# RPi-HAT_BUS-Controller_V0_1.net
KiCad netlist of a schematic drawn in EAGLE
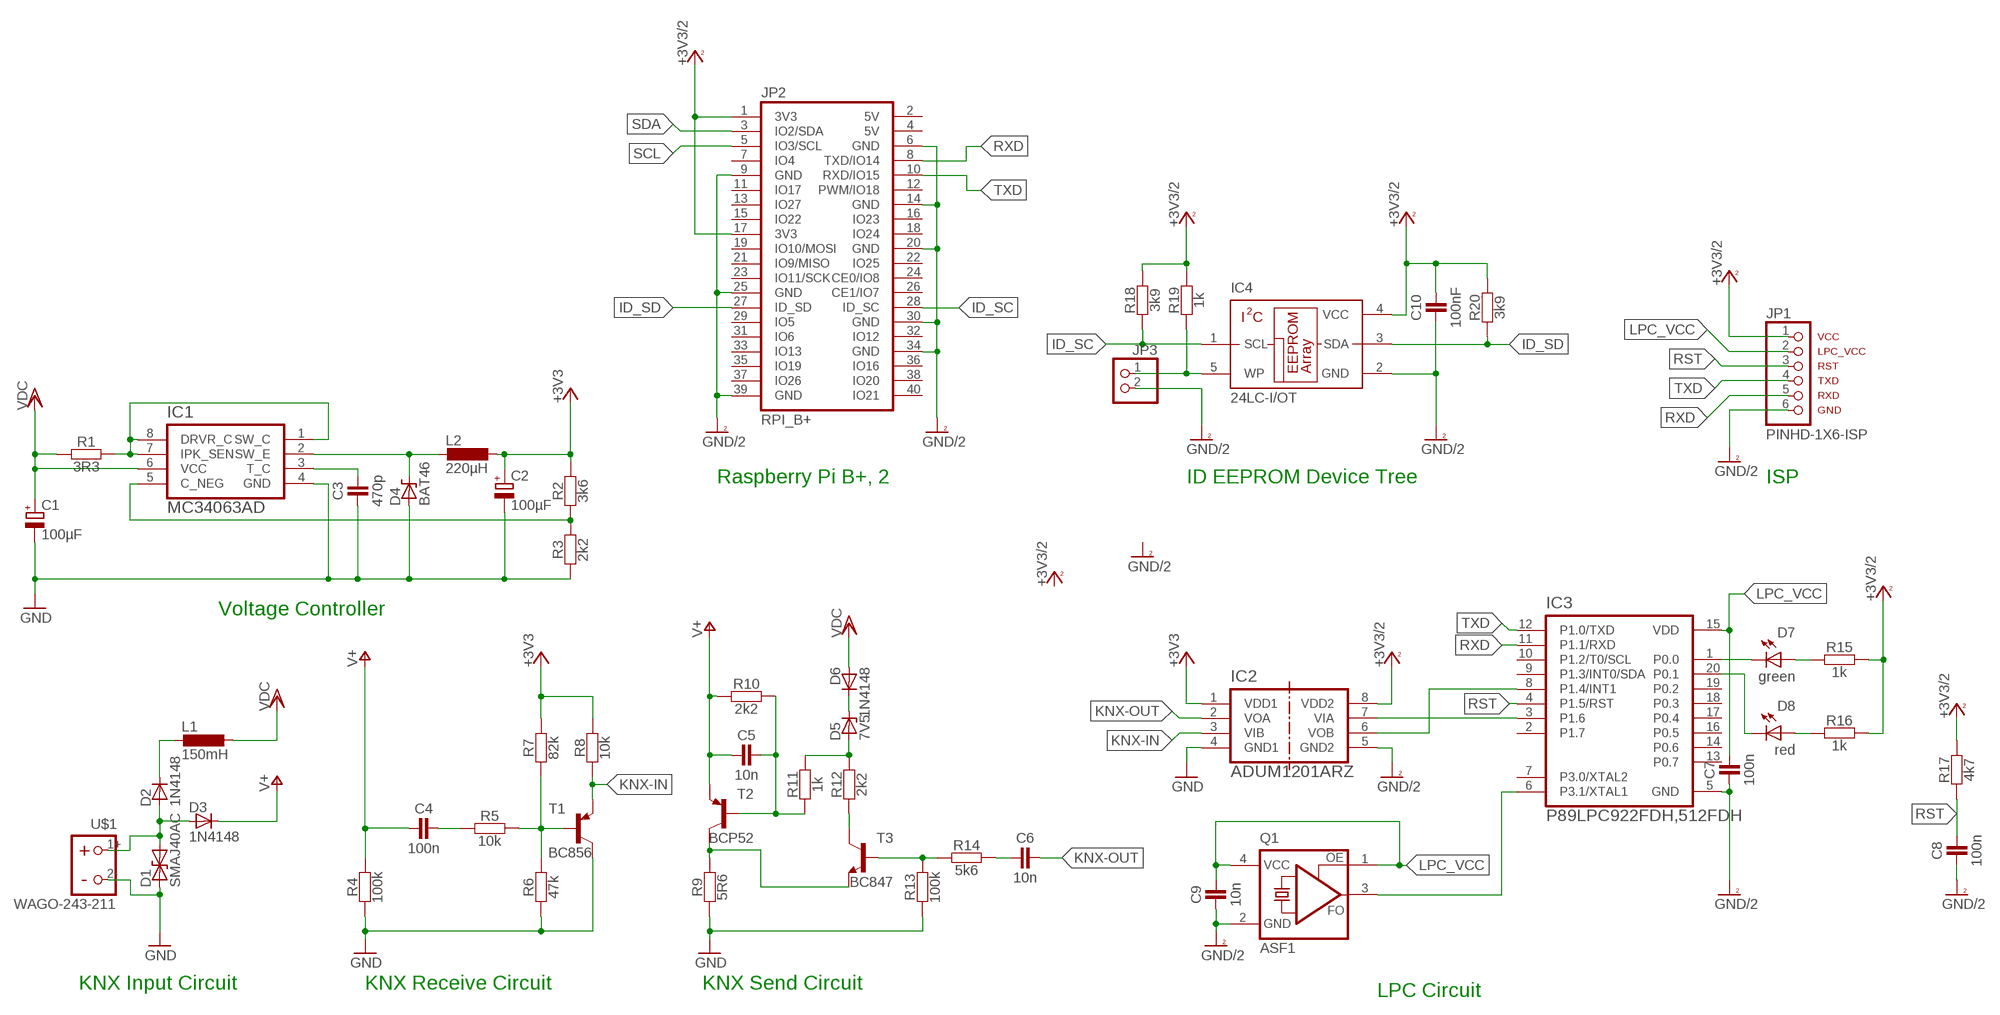
[diagram p0: schematic, sheet 1]

(export (version "E")
  (design (tool "Eeschema 10.0.6"))
  (components
    (comp (ref "C1")
      (value "100µF")
      (footprint "eagle-import:PANASONIC_D")
      (libsource (lib "eagle-import") (part "100µF,35V"))
    )
    (comp (ref "C2")
      (value "100µF")
      (footprint "eagle-import:PANASONIC_C")
      (libsource (lib "eagle-import") (part "100µF,6.3V"))
    )
    (comp (ref "C3")
      (value "470p")
      (footprint "eagle-import:R1206")
      (libsource (lib "eagle-import") (part "CAPACITORC1206"))
    )
    (comp (ref "C4")
      (value "100n")
      (footprint "eagle-import:R1206")
      (libsource (lib "eagle-import") (part "CAPACITORC1206"))
    )
    (comp (ref "C5")
      (value "10n")
      (footprint "eagle-import:R1206")
      (libsource (lib "eagle-import") (part "CAPACITORC1206"))
    )
    (comp (ref "C6")
      (value "10n")
      (footprint "eagle-import:R1206")
      (libsource (lib "eagle-import") (part "CAPACITORC1206"))
    )
    (comp (ref "C7")
      (value "100n")
      (footprint "eagle-import:R1206")
      (libsource (lib "eagle-import") (part "CAPACITORC1206"))
    )
    (comp (ref "C8")
      (value "100n")
      (footprint "eagle-import:R1206")
      (libsource (lib "eagle-import") (part "CAPACITORC1206"))
    )
    (comp (ref "C9")
      (value "10n")
      (footprint "eagle-import:R1206")
      (libsource (lib "eagle-import") (part "CAPACITORC1206"))
    )
    (comp (ref "C10")
      (value "100nF")
      (footprint "eagle-import:R1206")
      (libsource (lib "eagle-import") (part "CAPACITORC1206"))
    )
    (comp (ref "D1")
      (value "SMAJ40AC")
      (footprint "eagle-import:DO-214AC")
      (libsource (lib "eagle-import") (part "SMAJ40AC"))
    )
    (comp (ref "D2")
      (value "1N4148")
      (footprint "eagle-import:MINIMELF")
      (libsource (lib "eagle-import") (part "1N4148MINIMELF"))
    )
    (comp (ref "D3")
      (value "1N4148")
      (footprint "eagle-import:MINIMELF")
      (libsource (lib "eagle-import") (part "1N4148MINIMELF"))
    )
    (comp (ref "D4")
      (value "BAT46")
      (footprint "eagle-import:MINIMELF")
      (libsource (lib "eagle-import") (part "BAT46"))
    )
    (comp (ref "D5")
      (value "7V5")
      (footprint "eagle-import:MINIMELF")
      (libsource (lib "eagle-import") (part "Z-DIODE"))
    )
    (comp (ref "D6")
      (value "1N4148")
      (footprint "eagle-import:MINIMELF")
      (libsource (lib "eagle-import") (part "Diode_for_Selfbus-Projects_1N4148MINIMELF"))
    )
    (comp (ref "D7")
      (value "green")
      (footprint "eagle-import:CHIPLED_1206")
      (libsource (lib "eagle-import") (part "LED1206"))
    )
    (comp (ref "D8")
      (value "red")
      (footprint "eagle-import:CHIPLED_1206")
      (libsource (lib "eagle-import") (part "LED1206"))
    )
    (comp (ref "IC1")
      (value "MC34063AD")
      (footprint "eagle-import:SOIC127P600X175-8N")
      (libsource (lib "eagle-import") (part "MC34063AD"))
    )
    (comp (ref "IC2")
      (value "ADUM1201ARZ")
      (footprint "eagle-import:SOIC127P600X175-8N")
      (libsource (lib "eagle-import") (part "ADUM1201ARZ"))
    )
    (comp (ref "IC3")
      (value "P89LPC922FDH,512FDH")
      (footprint "eagle-import:SOP65P640X110-20N")
      (fields (field (name "MPN") "P89LPC922FDH,512"))
      (libsource (lib "eagle-import") (part "P89LPC922FDH,512FDH"))
    )
    (comp (ref "IC4")
      (value "24LC-I/OT")
      (footprint "eagle-import:SOT23-5")
      (libsource (lib "eagle-import") (part "24LC-I/OT"))
    )
    (comp (ref "JP1")
      (value "PINHD-1X6-ISP")
      (footprint "eagle-import:1X06")
      (libsource (lib "eagle-import") (part "PINHD-1X6-ISP"))
    )
    (comp (ref "JP2")
      (value "RPI_B+")
      (footprint "eagle-import:RPI-B+HAT")
      (libsource (lib "eagle-import") (part "RPI_B+"))
    )
    (comp (ref "JP3")
      (value "PINHD-1X2")
      (footprint "eagle-import:1X02")
      (libsource (lib "eagle-import") (part "PINHD-1X2"))
    )
    (comp (ref "L1")
      (value "150mH")
      (footprint "eagle-import:11P-L1")
      (libsource (lib "eagle-import") (part "150MH-L11PL1"))
    )
    (comp (ref "L2")
      (value "220µH")
      (footprint "eagle-import:2200-11.43")
      (libsource (lib "eagle-import") (part "220µH-SMCC11.43"))
    )
    (comp (ref "Q1")
      (value "ASF1")
      (footprint "eagle-import:ASF")
      (libsource (lib "eagle-import") (part "ASF1"))
    )
    (comp (ref "R1")
      (value "3R3")
      (footprint "eagle-import:R1206")
      (libsource (lib "eagle-import") (part "RESISTORR1206"))
    )
    (comp (ref "R2")
      (value "3k6")
      (footprint "eagle-import:R1206")
      (libsource (lib "eagle-import") (part "RESISTORR1206"))
    )
    (comp (ref "R3")
      (value "2k2")
      (footprint "eagle-import:R1206")
      (libsource (lib "eagle-import") (part "RESISTORR1206"))
    )
    (comp (ref "R4")
      (value "100k")
      (footprint "eagle-import:R1206")
      (libsource (lib "eagle-import") (part "RESISTORR1206"))
    )
    (comp (ref "R5")
      (value "10k")
      (footprint "eagle-import:R1206")
      (libsource (lib "eagle-import") (part "RESISTORR1206"))
    )
    (comp (ref "R6")
      (value "47k")
      (footprint "eagle-import:R1206")
      (libsource (lib "eagle-import") (part "RESISTORR1206"))
    )
    (comp (ref "R7")
      (value "82k")
      (footprint "eagle-import:R1206")
      (libsource (lib "eagle-import") (part "RESISTORR1206"))
    )
    (comp (ref "R8")
      (value "10k")
      (footprint "eagle-import:R1206")
      (libsource (lib "eagle-import") (part "RESISTORR1206"))
    )
    (comp (ref "R9")
      (value "5R6")
      (footprint "eagle-import:R1206")
      (libsource (lib "eagle-import") (part "RESISTORR1206"))
    )
    (comp (ref "R10")
      (value "2k2")
      (footprint "eagle-import:R1206")
      (libsource (lib "eagle-import") (part "RESISTORR1206"))
    )
    (comp (ref "R11")
      (value "1k")
      (footprint "eagle-import:R1206")
      (libsource (lib "eagle-import") (part "RESISTORR1206"))
    )
    (comp (ref "R12")
      (value "2k2")
      (footprint "eagle-import:R1206")
      (libsource (lib "eagle-import") (part "RESISTORR1206"))
    )
    (comp (ref "R13")
      (value "100k")
      (footprint "eagle-import:R1206")
      (libsource (lib "eagle-import") (part "RESISTORR1206"))
    )
    (comp (ref "R14")
      (value "5k6")
      (footprint "eagle-import:R1206")
      (libsource (lib "eagle-import") (part "RESISTORR1206"))
    )
    (comp (ref "R15")
      (value "1k")
      (footprint "eagle-import:R1206")
      (libsource (lib "eagle-import") (part "RESISTORR1206"))
    )
    (comp (ref "R16")
      (value "1k")
      (footprint "eagle-import:R1206")
      (libsource (lib "eagle-import") (part "RESISTORR1206"))
    )
    (comp (ref "R17")
      (value "4k7")
      (footprint "eagle-import:R1206")
      (libsource (lib "eagle-import") (part "RESISTORR1206"))
    )
    (comp (ref "R18")
      (value "3k9")
      (footprint "eagle-import:R1206")
      (libsource (lib "eagle-import") (part "RESISTORR1206"))
    )
    (comp (ref "R19")
      (value "1k")
      (footprint "eagle-import:R1206")
      (libsource (lib "eagle-import") (part "RESISTORR1206"))
    )
    (comp (ref "R20")
      (value "3k9")
      (footprint "eagle-import:R1206")
      (libsource (lib "eagle-import") (part "RESISTORR1206"))
    )
    (comp (ref "T1")
      (value "BC856")
      (footprint "eagle-import:SOT23")
      (libsource (lib "eagle-import") (part "PNPBC856"))
    )
    (comp (ref "T2")
      (value "BCP52")
      (footprint "eagle-import:SOT223")
      (libsource (lib "eagle-import") (part "PNPBCP52"))
    )
    (comp (ref "T3")
      (value "BC847")
      (footprint "eagle-import:SOT23")
      (libsource (lib "eagle-import") (part "NPN-BC847"))
    )
    (comp (ref "U$1")
      (value "WAGO-243-211")
      (footprint "eagle-import:WAGO-243-211")
      (libsource (lib "eagle-import") (part "WAGO-243-211"))
    )
  )
  (nets
    (net (code "1") (name "+3V3") (class "Default")
      (node (ref "C2") (pin "+") (pinfunction "+_+") (pintype "passive"))
      (node (ref "IC2") (pin "1") (pinfunction "VDD1_1") (pintype "power_in"))
      (node (ref "L2") (pin "1") (pinfunction "1_1") (pintype "passive"))
      (node (ref "R2") (pin "2") (pinfunction "2_2") (pintype "passive"))
      (node (ref "R7") (pin "2") (pinfunction "2_2") (pintype "passive"))
      (node (ref "R8") (pin "2") (pinfunction "2_2") (pintype "passive"))
    )
    (net (code "2") (name "+3V3{slash}2") (class "Default")
      (node (ref "C10") (pin "2") (pinfunction "2_2") (pintype "passive"))
      (node (ref "IC2") (pin "8") (pinfunction "VDD2_8") (pintype "power_in"))
      (node (ref "IC4") (pin "4") (pinfunction "VCC_4") (pintype "power_in"))
      (node (ref "JP1") (pin "1") (pinfunction "1_1") (pintype "passive"))
      (node (ref "JP2") (pin "1") (pinfunction "3V3_1") (pintype "passive"))
      (node (ref "JP2") (pin "17") (pinfunction "3V3_17") (pintype "passive"))
      (node (ref "R15") (pin "2") (pinfunction "2_2") (pintype "passive"))
      (node (ref "R16") (pin "2") (pinfunction "2_2") (pintype "passive"))
      (node (ref "R17") (pin "2") (pinfunction "2_2") (pintype "passive"))
      (node (ref "R18") (pin "2") (pinfunction "2_2") (pintype "passive"))
      (node (ref "R19") (pin "2") (pinfunction "2_2") (pintype "passive"))
      (node (ref "R20") (pin "2") (pinfunction "2_2") (pintype "passive"))
    )
    (net (code "3") (name "GND") (class "Default")
      (node (ref "C1") (pin "-") (pinfunction "-_-") (pintype "passive"))
      (node (ref "C2") (pin "-") (pinfunction "-_-") (pintype "passive"))
      (node (ref "C3") (pin "1") (pinfunction "1_1") (pintype "passive"))
      (node (ref "D1") (pin "A") (pinfunction "A_A") (pintype "passive"))
      (node (ref "D4") (pin "A") (pinfunction "A_A") (pintype "passive"))
      (node (ref "IC1") (pin "4") (pinfunction "GND_4") (pintype "passive"))
      (node (ref "IC2") (pin "4") (pinfunction "GND1_4") (pintype "passive"))
      (node (ref "R13") (pin "1") (pinfunction "1_1") (pintype "passive"))
      (node (ref "R3") (pin "1") (pinfunction "1_1") (pintype "passive"))
      (node (ref "R4") (pin "1") (pinfunction "1_1") (pintype "passive"))
      (node (ref "R6") (pin "1") (pinfunction "1_1") (pintype "passive"))
      (node (ref "R9") (pin "1") (pinfunction "1_1") (pintype "passive"))
      (node (ref "T1") (pin "3") (pinfunction "C_3") (pintype "passive"))
      (node (ref "U$1") (pin "2-") (pinfunction "2-_2-") (pintype "passive"))
    )
    (net (code "4") (name "GND{slash}2") (class "Default")
      (node (ref "C10") (pin "1") (pinfunction "1_1") (pintype "passive"))
      (node (ref "C7") (pin "1") (pinfunction "1_1") (pintype "passive"))
      (node (ref "C8") (pin "1") (pinfunction "1_1") (pintype "passive"))
      (node (ref "C9") (pin "1") (pinfunction "1_1") (pintype "passive"))
      (node (ref "IC2") (pin "5") (pinfunction "GND2_5") (pintype "passive"))
      (node (ref "IC3") (pin "5") (pinfunction "GND_5") (pintype "passive"))
      (node (ref "IC4") (pin "2") (pinfunction "GND_2") (pintype "power_in"))
      (node (ref "JP1") (pin "6") (pinfunction "6_6") (pintype "passive"))
      (node (ref "JP2") (pin "14") (pinfunction "GND_14") (pintype "passive"))
      (node (ref "JP2") (pin "20") (pinfunction "GND_20") (pintype "passive"))
      (node (ref "JP2") (pin "25") (pinfunction "GND_25") (pintype "passive"))
      (node (ref "JP2") (pin "30") (pinfunction "GND_30") (pintype "bidirectional"))
      (node (ref "JP2") (pin "34") (pinfunction "GND_34") (pintype "bidirectional"))
      (node (ref "JP2") (pin "39") (pinfunction "GND_39") (pintype "bidirectional"))
      (node (ref "JP2") (pin "6") (pinfunction "GND_6") (pintype "passive"))
      (node (ref "JP2") (pin "9") (pinfunction "GND_9") (pintype "passive"))
      (node (ref "JP3") (pin "2") (pinfunction "2_2") (pintype "passive"))
      (node (ref "Q1") (pin "2") (pinfunction "GND_2") (pintype "power_in"))
    )
    (net (code "5") (name "ID_SC") (class "Default")
      (node (ref "IC4") (pin "1") (pinfunction "SCL_1") (pintype "bidirectional"))
      (node (ref "JP2") (pin "28") (pinfunction "ID_SC_28") (pintype "bidirectional"))
      (node (ref "R18") (pin "1") (pinfunction "1_1") (pintype "passive"))
    )
    (net (code "6") (name "ID_SD") (class "Default")
      (node (ref "IC4") (pin "3") (pinfunction "SDA_3") (pintype "bidirectional"))
      (node (ref "JP2") (pin "27") (pinfunction "ID_SD_27") (pintype "bidirectional"))
      (node (ref "R20") (pin "1") (pinfunction "1_1") (pintype "passive"))
    )
    (net (code "7") (name "KNX-IN") (class "Default")
      (node (ref "IC2") (pin "3") (pinfunction "VIB_3") (pintype "input"))
      (node (ref "R8") (pin "1") (pinfunction "1_1") (pintype "passive"))
      (node (ref "T1") (pin "2") (pinfunction "E_2") (pintype "passive"))
    )
    (net (code "8") (name "KNX-OUT") (class "Default")
      (node (ref "C6") (pin "2") (pinfunction "2_2") (pintype "passive"))
      (node (ref "IC2") (pin "2") (pinfunction "VOA_2") (pintype "output"))
    )
    (net (code "9") (name "LPC_VCC") (class "Default")
      (node (ref "C7") (pin "2") (pinfunction "2_2") (pintype "passive"))
      (node (ref "C9") (pin "2") (pinfunction "2_2") (pintype "passive"))
      (node (ref "IC3") (pin "15") (pinfunction "VDD_15") (pintype "power_in"))
      (node (ref "JP1") (pin "2") (pinfunction "2_2") (pintype "passive"))
      (node (ref "Q1") (pin "1") (pinfunction "OE_1") (pintype "input"))
      (node (ref "Q1") (pin "4") (pinfunction "VCC_4") (pintype "power_in"))
    )
    (net (code "10") (name "Net-(C4-Pad2)") (class "Default")
      (node (ref "C4") (pin "2") (pinfunction "2_2") (pintype "passive"))
      (node (ref "R5") (pin "1") (pinfunction "1_1") (pintype "passive"))
    )
    (net (code "11") (name "Net-(C6-Pad1)") (class "Default")
      (node (ref "C6") (pin "1") (pinfunction "1_1") (pintype "passive"))
      (node (ref "R14") (pin "2") (pinfunction "2_2") (pintype "passive"))
    )
    (net (code "12") (name "Net-(D1-PadC)") (class "Default")
      (node (ref "D1") (pin "C") (pinfunction "C_C") (pintype "passive"))
      (node (ref "D2") (pin "A") (pinfunction "A_A") (pintype "passive"))
      (node (ref "D3") (pin "A") (pinfunction "A_A") (pintype "passive"))
      (node (ref "U$1") (pin "1+") (pinfunction "1+_1+") (pintype "passive"))
    )
    (net (code "13") (name "Net-(D2-PadC)") (class "Default")
      (node (ref "D2") (pin "C") (pinfunction "C_C") (pintype "passive"))
      (node (ref "L1") (pin "2") (pinfunction "2_2") (pintype "passive"))
    )
    (net (code "14") (name "Net-(D5-PadA)") (class "Default")
      (node (ref "D5") (pin "A") (pinfunction "A_A") (pintype "passive"))
      (node (ref "R11") (pin "2") (pinfunction "2_2") (pintype "passive"))
      (node (ref "R12") (pin "2") (pinfunction "2_2") (pintype "passive"))
    )
    (net (code "15") (name "Net-(D5-PadC)") (class "Default")
      (node (ref "D5") (pin "C") (pinfunction "C_C") (pintype "passive"))
      (node (ref "D6") (pin "C") (pinfunction "C_C") (pintype "passive"))
    )
    (net (code "16") (name "Net-(D7-PadA)") (class "Default")
      (node (ref "D7") (pin "A") (pinfunction "A_A") (pintype "passive"))
      (node (ref "R15") (pin "1") (pinfunction "1_1") (pintype "passive"))
    )
    (net (code "17") (name "Net-(D8-PadA)") (class "Default")
      (node (ref "D8") (pin "A") (pinfunction "A_A") (pintype "passive"))
      (node (ref "R16") (pin "1") (pinfunction "1_1") (pintype "passive"))
    )
    (net (code "18") (name "Net-(IC1-C_NEG)") (class "Default")
      (node (ref "IC1") (pin "5") (pinfunction "C_NEG_5") (pintype "input"))
      (node (ref "R2") (pin "1") (pinfunction "1_1") (pintype "passive"))
      (node (ref "R3") (pin "2") (pinfunction "2_2") (pintype "passive"))
    )
    (net (code "19") (name "Net-(IC1-DRVR_C)") (class "Default")
      (node (ref "IC1") (pin "1") (pinfunction "SW_C_1") (pintype "output"))
      (node (ref "IC1") (pin "7") (pinfunction "IPK_SEN_7") (pintype "input"))
      (node (ref "IC1") (pin "8") (pinfunction "DRVR_C_8") (pintype "input"))
      (node (ref "R1") (pin "2") (pinfunction "2_2") (pintype "passive"))
    )
    (net (code "20") (name "Net-(IC1-SW_E)") (class "Default")
      (node (ref "D4") (pin "C") (pinfunction "C_C") (pintype "passive"))
      (node (ref "IC1") (pin "2") (pinfunction "SW_E_2") (pintype "output"))
      (node (ref "L2") (pin "2") (pinfunction "2_2") (pintype "passive"))
    )
    (net (code "21") (name "Net-(IC1-T_C)") (class "Default")
      (node (ref "C3") (pin "2") (pinfunction "2_2") (pintype "passive"))
      (node (ref "IC1") (pin "3") (pinfunction "T_C_3") (pintype "output"))
    )
    (net (code "22") (name "Net-(IC2-VIA)") (class "Default")
      (node (ref "IC2") (pin "7") (pinfunction "VIA_7") (pintype "input"))
      (node (ref "IC3") (pin "3") (pinfunction "P1.6_3") (pintype "bidirectional"))
    )
    (net (code "23") (name "Net-(IC2-VOB)") (class "Default")
      (node (ref "IC2") (pin "6") (pinfunction "VOB_6") (pintype "output"))
      (node (ref "IC3") (pin "8") (pinfunction "P1.4/INT1_8") (pintype "bidirectional"))
    )
    (net (code "24") (name "Net-(IC3-P0.0)") (class "Default")
      (node (ref "D7") (pin "C") (pinfunction "C_C") (pintype "passive"))
      (node (ref "IC3") (pin "1") (pinfunction "P0.0_1") (pintype "bidirectional"))
    )
    (net (code "25") (name "Net-(IC3-P0.1)") (class "Default")
      (node (ref "D8") (pin "C") (pinfunction "C_C") (pintype "passive"))
      (node (ref "IC3") (pin "20") (pinfunction "P0.1_20") (pintype "bidirectional"))
    )
    (net (code "26") (name "Net-(IC3-P3.1{slash}XTAL1)") (class "Default")
      (node (ref "IC3") (pin "6") (pinfunction "P3.1/XTAL1_6") (pintype "bidirectional"))
      (node (ref "Q1") (pin "3") (pinfunction "FO_3") (pintype "output"))
    )
    (net (code "27") (name "Net-(IC4-WP)") (class "Default")
      (node (ref "IC4") (pin "5") (pinfunction "WP_5") (pintype "bidirectional"))
      (node (ref "JP3") (pin "1") (pinfunction "1_1") (pintype "passive"))
      (node (ref "R19") (pin "1") (pinfunction "1_1") (pintype "passive"))
    )
    (net (code "28") (name "Net-(T1-B)") (class "Default")
      (node (ref "R5") (pin "2") (pinfunction "2_2") (pintype "passive"))
      (node (ref "R6") (pin "2") (pinfunction "2_2") (pintype "passive"))
      (node (ref "R7") (pin "1") (pinfunction "1_1") (pintype "passive"))
      (node (ref "T1") (pin "1") (pinfunction "B_1") (pintype "passive"))
    )
    (net (code "29") (name "Net-(T2-B)") (class "Default")
      (node (ref "C5") (pin "2") (pinfunction "2_2") (pintype "passive"))
      (node (ref "R10") (pin "2") (pinfunction "2_2") (pintype "passive"))
      (node (ref "R11") (pin "1") (pinfunction "1_1") (pintype "passive"))
      (node (ref "T2") (pin "1") (pinfunction "B_1") (pintype "passive"))
    )
    (net (code "30") (name "Net-(T3-B)") (class "Default")
      (node (ref "R13") (pin "2") (pinfunction "2_2") (pintype "passive"))
      (node (ref "R14") (pin "1") (pinfunction "1_1") (pintype "passive"))
      (node (ref "T3") (pin "1") (pinfunction "B_1") (pintype "passive"))
    )
    (net (code "31") (name "Net-(T3-C)") (class "Default")
      (node (ref "R12") (pin "1") (pinfunction "1_1") (pintype "passive"))
      (node (ref "T3") (pin "3") (pinfunction "C_3") (pintype "passive"))
    )
    (net (code "32") (name "Net-(T3-E)") (class "Default")
      (node (ref "R9") (pin "2") (pinfunction "2_2") (pintype "passive"))
      (node (ref "T2") (pin "2") (pinfunction "C_2") (pintype "passive"))
      (node (ref "T2") (pin "4") (pinfunction "C_4") (pintype "passive"))
      (node (ref "T3") (pin "2") (pinfunction "E_2") (pintype "passive"))
    )
    (net (code "33") (name "RST") (class "Default")
      (node (ref "C8") (pin "2") (pinfunction "2_2") (pintype "passive"))
      (node (ref "IC3") (pin "4") (pinfunction "P1.5/RST_4") (pintype "input"))
      (node (ref "JP1") (pin "3") (pinfunction "3_3") (pintype "passive"))
      (node (ref "R17") (pin "1") (pinfunction "1_1") (pintype "passive"))
    )
    (net (code "34") (name "RXD") (class "Default")
      (node (ref "IC3") (pin "11") (pinfunction "P1.1/RXD_11") (pintype "bidirectional"))
      (node (ref "JP1") (pin "5") (pinfunction "5_5") (pintype "passive"))
      (node (ref "JP2") (pin "8") (pinfunction "TXD/IO14_8") (pintype "passive"))
    )
    (net (code "35") (name "SCL") (class "Default")
      (node (ref "JP2") (pin "5") (pinfunction "IO3/SCL_5") (pintype "passive"))
    )
    (net (code "36") (name "SDA") (class "Default")
      (node (ref "JP2") (pin "3") (pinfunction "IO2/SDA_3") (pintype "passive"))
    )
    (net (code "37") (name "TXD") (class "Default")
      (node (ref "IC3") (pin "12") (pinfunction "P1.0/TXD_12") (pintype "bidirectional"))
      (node (ref "JP1") (pin "4") (pinfunction "4_4") (pintype "passive"))
      (node (ref "JP2") (pin "10") (pinfunction "RXD/IO15_10") (pintype "passive"))
    )
    (net (code "38") (name "V+") (class "Default")
      (node (ref "C4") (pin "1") (pinfunction "1_1") (pintype "passive"))
      (node (ref "C5") (pin "1") (pinfunction "1_1") (pintype "passive"))
      (node (ref "D3") (pin "C") (pinfunction "C_C") (pintype "passive"))
      (node (ref "R10") (pin "1") (pinfunction "1_1") (pintype "passive"))
      (node (ref "R4") (pin "2") (pinfunction "2_2") (pintype "passive"))
      (node (ref "T2") (pin "3") (pinfunction "E_3") (pintype "passive"))
    )
    (net (code "39") (name "VDC") (class "Default")
      (node (ref "C1") (pin "+") (pinfunction "+_+") (pintype "passive"))
      (node (ref "D6") (pin "A") (pinfunction "A_A") (pintype "passive"))
      (node (ref "IC1") (pin "6") (pinfunction "VCC_6") (pintype "power_in"))
      (node (ref "L1") (pin "1") (pinfunction "1_1") (pintype "passive"))
      (node (ref "R1") (pin "1") (pinfunction "1_1") (pintype "passive"))
    )
    (net (code "40") (name "unconnected-(IC3-P0.2-Pad19)") (class "Default")
      (node (ref "IC3") (pin "19") (pinfunction "P0.2_19") (pintype "bidirectional"))
    )
    (net (code "41") (name "unconnected-(IC3-P0.3-Pad18)") (class "Default")
      (node (ref "IC3") (pin "18") (pinfunction "P0.3_18") (pintype "bidirectional"))
    )
    (net (code "42") (name "unconnected-(IC3-P0.4-Pad17)") (class "Default")
      (node (ref "IC3") (pin "17") (pinfunction "P0.4_17") (pintype "bidirectional"))
    )
    (net (code "43") (name "unconnected-(IC3-P0.5-Pad16)") (class "Default")
      (node (ref "IC3") (pin "16") (pinfunction "P0.5_16") (pintype "bidirectional"))
    )
    (net (code "44") (name "unconnected-(IC3-P0.6-Pad14)") (class "Default")
      (node (ref "IC3") (pin "14") (pinfunction "P0.6_14") (pintype "bidirectional"))
    )
    (net (code "45") (name "unconnected-(IC3-P0.7-Pad13)") (class "Default")
      (node (ref "IC3") (pin "13") (pinfunction "P0.7_13") (pintype "passive"))
    )
    (net (code "46") (name "unconnected-(IC3-P1.2{slash}T0{slash}SCL-Pad10)") (class "Default")
      (node (ref "IC3") (pin "10") (pinfunction "P1.2/T0/SCL_10") (pintype "bidirectional"))
    )
    (net (code "47") (name "unconnected-(IC3-P1.3{slash}INT0{slash}SDA-Pad9)") (class "Default")
      (node (ref "IC3") (pin "9") (pinfunction "P1.3/INT0/SDA_9") (pintype "bidirectional"))
    )
    (net (code "48") (name "unconnected-(IC3-P1.7-Pad2)") (class "Default")
      (node (ref "IC3") (pin "2") (pinfunction "P1.7_2") (pintype "bidirectional"))
    )
    (net (code "49") (name "unconnected-(IC3-P3.0{slash}XTAL2-Pad7)") (class "Default")
      (node (ref "IC3") (pin "7") (pinfunction "P3.0/XTAL2_7") (pintype "bidirectional"))
    )
    (net (code "50") (name "unconnected-(JP2-5V-Pad2)") (class "Default")
      (node (ref "JP2") (pin "2") (pinfunction "5V_2") (pintype "passive"))
    )
    (net (code "51") (name "unconnected-(JP2-5V-Pad4)") (class "Default")
      (node (ref "JP2") (pin "4") (pinfunction "5V_4") (pintype "passive"))
    )
    (net (code "52") (name "unconnected-(JP2-CE0{slash}IO8-Pad24)") (class "Default")
      (node (ref "JP2") (pin "24") (pinfunction "CE0/IO8_24") (pintype "passive"))
    )
    (net (code "53") (name "unconnected-(JP2-CE1{slash}IO7-Pad26)") (class "Default")
      (node (ref "JP2") (pin "26") (pinfunction "CE1/IO7_26") (pintype "passive"))
    )
    (net (code "54") (name "unconnected-(JP2-IO4-Pad7)") (class "Default")
      (node (ref "JP2") (pin "7") (pinfunction "IO4_7") (pintype "passive"))
    )
    (net (code "55") (name "unconnected-(JP2-IO5-Pad29)") (class "Default")
      (node (ref "JP2") (pin "29") (pinfunction "IO5_29") (pintype "bidirectional"))
    )
    (net (code "56") (name "unconnected-(JP2-IO6-Pad31)") (class "Default")
      (node (ref "JP2") (pin "31") (pinfunction "IO6_31") (pintype "bidirectional"))
    )
    (net (code "57") (name "unconnected-(JP2-IO9{slash}MISO-Pad21)") (class "Default")
      (node (ref "JP2") (pin "21") (pinfunction "IO9/MISO_21") (pintype "passive"))
    )
    (net (code "58") (name "unconnected-(JP2-IO10{slash}MOSI-Pad19)") (class "Default")
      (node (ref "JP2") (pin "19") (pinfunction "IO10/MOSI_19") (pintype "passive"))
    )
    (net (code "59") (name "unconnected-(JP2-IO11{slash}SCK-Pad23)") (class "Default")
      (node (ref "JP2") (pin "23") (pinfunction "IO11/SCK_23") (pintype "passive"))
    )
    (net (code "60") (name "unconnected-(JP2-IO12-Pad32)") (class "Default")
      (node (ref "JP2") (pin "32") (pinfunction "IO12_32") (pintype "bidirectional"))
    )
    (net (code "61") (name "unconnected-(JP2-IO13-Pad33)") (class "Default")
      (node (ref "JP2") (pin "33") (pinfunction "IO13_33") (pintype "bidirectional"))
    )
    (net (code "62") (name "unconnected-(JP2-IO16-Pad36)") (class "Default")
      (node (ref "JP2") (pin "36") (pinfunction "IO16_36") (pintype "bidirectional"))
    )
    (net (code "63") (name "unconnected-(JP2-IO17-Pad11)") (class "Default")
      (node (ref "JP2") (pin "11") (pinfunction "IO17_11") (pintype "passive"))
    )
    (net (code "64") (name "unconnected-(JP2-IO19-Pad35)") (class "Default")
      (node (ref "JP2") (pin "35") (pinfunction "IO19_35") (pintype "bidirectional"))
    )
    (net (code "65") (name "unconnected-(JP2-IO20-Pad38)") (class "Default")
      (node (ref "JP2") (pin "38") (pinfunction "IO20_38") (pintype "bidirectional"))
    )
    (net (code "66") (name "unconnected-(JP2-IO21-Pad40)") (class "Default")
      (node (ref "JP2") (pin "40") (pinfunction "IO21_40") (pintype "bidirectional"))
    )
    (net (code "67") (name "unconnected-(JP2-IO22-Pad15)") (class "Default")
      (node (ref "JP2") (pin "15") (pinfunction "IO22_15") (pintype "passive"))
    )
    (net (code "68") (name "unconnected-(JP2-IO23-Pad16)") (class "Default")
      (node (ref "JP2") (pin "16") (pinfunction "IO23_16") (pintype "passive"))
    )
    (net (code "69") (name "unconnected-(JP2-IO24-Pad18)") (class "Default")
      (node (ref "JP2") (pin "18") (pinfunction "IO24_18") (pintype "passive"))
    )
    (net (code "70") (name "unconnected-(JP2-IO25-Pad22)") (class "Default")
      (node (ref "JP2") (pin "22") (pinfunction "IO25_22") (pintype "passive"))
    )
    (net (code "71") (name "unconnected-(JP2-IO26-Pad37)") (class "Default")
      (node (ref "JP2") (pin "37") (pinfunction "IO26_37") (pintype "bidirectional"))
    )
    (net (code "72") (name "unconnected-(JP2-IO27-Pad13)") (class "Default")
      (node (ref "JP2") (pin "13") (pinfunction "IO27_13") (pintype "passive"))
    )
    (net (code "73") (name "unconnected-(JP2-PWM{slash}IO18-Pad12)") (class "Default")
      (node (ref "JP2") (pin "12") (pinfunction "PWM/IO18_12") (pintype "passive"))
    )
  )
)
